# oxvox.net
KiCad netlist of a schematic drawn in EAGLE
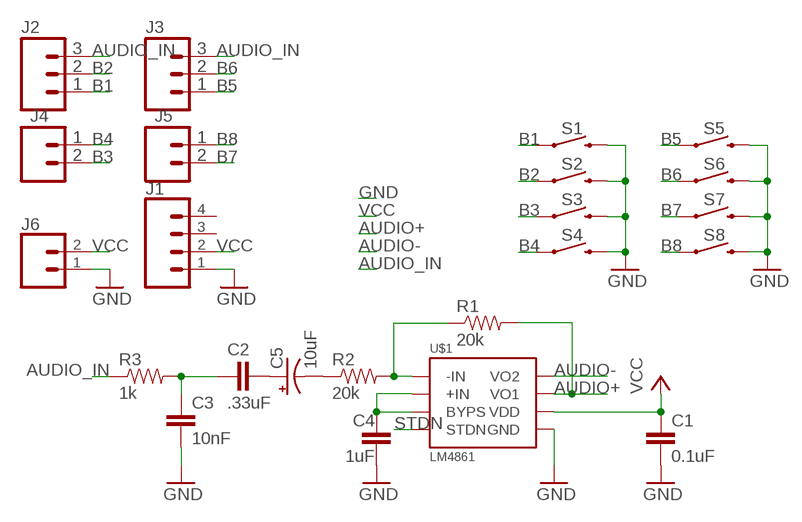
[diagram p0: schematic, sheet 1]

(export (version "E")
  (design (tool "Eeschema 10.0.6"))
  (components
    (comp (ref "C1")
      (value "0.1uF")
      (footprint "eagle-import:0603-CAP")
      (libsource (lib "eagle-import") (part "CAP0603-CAP"))
    )
    (comp (ref "C2")
      (value ".33uF")
      (footprint "eagle-import:0603-CAP")
      (libsource (lib "eagle-import") (part "CAP0603-CAP"))
    )
    (comp (ref "C3")
      (value "10nF")
      (footprint "eagle-import:0603-CAP")
      (libsource (lib "eagle-import") (part "CAP0603-CAP"))
    )
    (comp (ref "C4")
      (value "1uF")
      (footprint "eagle-import:0603-CAP")
      (libsource (lib "eagle-import") (part "CAP0603-CAP"))
    )
    (comp (ref "C5")
      (value "10uF")
      (footprint "eagle-import:RADIAL_SMT_4MM")
      (libsource (lib "eagle-import") (part "RADIAL-CAP4MM"))
    )
    (comp (ref "J1")
      (value "CONN_04")
      (footprint "eagle-import:1X04")
      (libsource (lib "eagle-import") (part "CONN_04"))
    )
    (comp (ref "J2")
      (value "M03-PTH_LONG_NO_SILK_BOT")
      (footprint "eagle-import:M03_LONG_NO_SILK_BOTTOM")
      (libsource (lib "eagle-import") (part "M03-PTH_LONG_NO_SILK_BOT"))
    )
    (comp (ref "J3")
      (value "M03-PTH_LONG_NO_SILK_BOT")
      (footprint "eagle-import:M03_LONG_NO_SILK_BOTTOM")
      (libsource (lib "eagle-import") (part "M03-PTH_LONG_NO_SILK_BOT"))
    )
    (comp (ref "J4")
      (value "M02-PTH_LONG_NO_SILK_BOT")
      (footprint "eagle-import:M02_LONG_NO_SILK_BOTTOM")
      (libsource (lib "eagle-import") (part "M02-PTH_LONG_NO_SILK_BOT"))
    )
    (comp (ref "J5")
      (value "M02-PTH_LONG_NO_SILK_BOT")
      (footprint "eagle-import:M02_LONG_NO_SILK_BOTTOM")
      (libsource (lib "eagle-import") (part "M02-PTH_LONG_NO_SILK_BOT"))
    )
    (comp (ref "J6")
      (value "CONN_02")
      (footprint "eagle-import:1X02")
      (libsource (lib "eagle-import") (part "CONN_02"))
    )
    (comp (ref "R1")
      (value "20k")
      (footprint "eagle-import:0805")
      (libsource (lib "eagle-import") (part "RESISTOR0805-RES"))
    )
    (comp (ref "R2")
      (value "20k")
      (footprint "eagle-import:0805")
      (libsource (lib "eagle-import") (part "RESISTOR0805-RES"))
    )
    (comp (ref "R3")
      (value "1k")
      (footprint "eagle-import:0603-RES")
      (libsource (lib "eagle-import") (part "RESISTOR0603-RES"))
    )
    (comp (ref "S1")
      (value "MOMENTARY-SWITCH-SPST-PTH-6.0MM-KIT-ALL2")
      (footprint "eagle-import:TACTILE_SWITCH_PTH_6.0MM_KIT_NOSILK")
      (libsource (lib "eagle-import") (part "MOMENTARY-SWITCH-SPST-PTH-6.0MM-KIT-ALL2"))
    )
    (comp (ref "S2")
      (value "MOMENTARY-SWITCH-SPST-PTH-6.0MM-KIT-ALL2")
      (footprint "eagle-import:TACTILE_SWITCH_PTH_6.0MM_KIT_NOSILK")
      (libsource (lib "eagle-import") (part "MOMENTARY-SWITCH-SPST-PTH-6.0MM-KIT-ALL2"))
    )
    (comp (ref "S3")
      (value "MOMENTARY-SWITCH-SPST-PTH-6.0MM-KIT-ALL2")
      (footprint "eagle-import:TACTILE_SWITCH_PTH_6.0MM_KIT_NOSILK")
      (libsource (lib "eagle-import") (part "MOMENTARY-SWITCH-SPST-PTH-6.0MM-KIT-ALL2"))
    )
    (comp (ref "S4")
      (value "MOMENTARY-SWITCH-SPST-PTH-6.0MM-KIT-ALL2")
      (footprint "eagle-import:TACTILE_SWITCH_PTH_6.0MM_KIT_NOSILK")
      (libsource (lib "eagle-import") (part "MOMENTARY-SWITCH-SPST-PTH-6.0MM-KIT-ALL2"))
    )
    (comp (ref "S5")
      (value "MOMENTARY-SWITCH-SPST-PTH-6.0MM-KIT-ALL2")
      (footprint "eagle-import:TACTILE_SWITCH_PTH_6.0MM_KIT_NOSILK")
      (libsource (lib "eagle-import") (part "MOMENTARY-SWITCH-SPST-PTH-6.0MM-KIT-ALL2"))
    )
    (comp (ref "S6")
      (value "MOMENTARY-SWITCH-SPST-PTH-6.0MM-KIT-ALL2")
      (footprint "eagle-import:TACTILE_SWITCH_PTH_6.0MM_KIT_NOSILK")
      (libsource (lib "eagle-import") (part "MOMENTARY-SWITCH-SPST-PTH-6.0MM-KIT-ALL2"))
    )
    (comp (ref "S7")
      (value "MOMENTARY-SWITCH-SPST-PTH-6.0MM-KIT-ALL2")
      (footprint "eagle-import:TACTILE_SWITCH_PTH_6.0MM_KIT_NOSILK")
      (libsource (lib "eagle-import") (part "MOMENTARY-SWITCH-SPST-PTH-6.0MM-KIT-ALL2"))
    )
    (comp (ref "S8")
      (value "MOMENTARY-SWITCH-SPST-PTH-6.0MM-KIT-ALL2")
      (footprint "eagle-import:TACTILE_SWITCH_PTH_6.0MM_KIT_NOSILK")
      (libsource (lib "eagle-import") (part "MOMENTARY-SWITCH-SPST-PTH-6.0MM-KIT-ALL2"))
    )
    (comp (ref "U$1")
      (value "LM4861")
      (footprint "eagle-import:8-SOIC")
      (libsource (lib "eagle-import") (part "LM4861"))
    )
  )
  (nets
    (net (code "1") (name "/AUDIO+") (class "Default")
      (node (ref "R1") (pin "2") (pinfunction "2_2") (pintype "passive"))
      (node (ref "U$1") (pin "P$5") (pinfunction "VO1_P$5") (pintype "bidirectional"))
    )
    (net (code "2") (name "/AUDIO-") (class "Default")
      (node (ref "U$1") (pin "P$8") (pinfunction "VO2_P$8") (pintype "bidirectional"))
    )
    (net (code "3") (name "/AUDIO_IN") (class "Default")
      (node (ref "J2") (pin "P$3") (pinfunction "P$3_P$3") (pintype "bidirectional"))
      (node (ref "J3") (pin "P$3") (pinfunction "P$3_P$3") (pintype "bidirectional"))
      (node (ref "R3") (pin "1") (pinfunction "1_1") (pintype "passive"))
    )
    (net (code "4") (name "/B1") (class "Default")
      (node (ref "J2") (pin "P$1") (pinfunction "P$1_P$1") (pintype "bidirectional"))
      (node (ref "S1") (pin "1") (pinfunction "1_1") (pintype "passive"))
      (node (ref "S1") (pin "2") (pinfunction "1_2") (pintype "passive"))
    )
    (net (code "5") (name "/B2") (class "Default")
      (node (ref "J2") (pin "P$2") (pinfunction "P$2_P$2") (pintype "bidirectional"))
      (node (ref "S2") (pin "1") (pinfunction "1_1") (pintype "passive"))
      (node (ref "S2") (pin "2") (pinfunction "1_2") (pintype "passive"))
    )
    (net (code "6") (name "/B3") (class "Default")
      (node (ref "J4") (pin "P$2") (pinfunction "P$2_P$2") (pintype "bidirectional"))
      (node (ref "S3") (pin "1") (pinfunction "1_1") (pintype "passive"))
      (node (ref "S3") (pin "2") (pinfunction "1_2") (pintype "passive"))
    )
    (net (code "7") (name "/B4") (class "Default")
      (node (ref "J4") (pin "P$1") (pinfunction "P$1_P$1") (pintype "bidirectional"))
      (node (ref "S4") (pin "1") (pinfunction "1_1") (pintype "passive"))
      (node (ref "S4") (pin "2") (pinfunction "1_2") (pintype "passive"))
    )
    (net (code "8") (name "/B5") (class "Default")
      (node (ref "J3") (pin "P$1") (pinfunction "P$1_P$1") (pintype "bidirectional"))
      (node (ref "S5") (pin "1") (pinfunction "1_1") (pintype "passive"))
      (node (ref "S5") (pin "2") (pinfunction "1_2") (pintype "passive"))
    )
    (net (code "9") (name "/B6") (class "Default")
      (node (ref "J3") (pin "P$2") (pinfunction "P$2_P$2") (pintype "bidirectional"))
      (node (ref "S6") (pin "1") (pinfunction "1_1") (pintype "passive"))
      (node (ref "S6") (pin "2") (pinfunction "1_2") (pintype "passive"))
    )
    (net (code "10") (name "/B7") (class "Default")
      (node (ref "J5") (pin "P$2") (pinfunction "P$2_P$2") (pintype "bidirectional"))
      (node (ref "S7") (pin "1") (pinfunction "1_1") (pintype "passive"))
      (node (ref "S7") (pin "2") (pinfunction "1_2") (pintype "passive"))
    )
    (net (code "11") (name "/B8") (class "Default")
      (node (ref "J5") (pin "P$1") (pinfunction "P$1_P$1") (pintype "bidirectional"))
      (node (ref "S8") (pin "1") (pinfunction "1_1") (pintype "passive"))
      (node (ref "S8") (pin "2") (pinfunction "1_2") (pintype "passive"))
    )
    (net (code "12") (name "/STDN") (class "Default")
      (node (ref "U$1") (pin "P$1") (pinfunction "STDN_P$1") (pintype "bidirectional"))
    )
    (net (code "13") (name "GND") (class "Default")
      (node (ref "C1") (pin "2") (pinfunction "2_2") (pintype "passive"))
      (node (ref "C3") (pin "2") (pinfunction "2_2") (pintype "passive"))
      (node (ref "C4") (pin "2") (pinfunction "2_2") (pintype "passive"))
      (node (ref "J1") (pin "1") (pinfunction "1_1") (pintype "passive"))
      (node (ref "J6") (pin "1") (pinfunction "1_1") (pintype "passive"))
      (node (ref "S1") (pin "3") (pinfunction "2_3") (pintype "passive"))
      (node (ref "S1") (pin "4") (pinfunction "2_4") (pintype "passive"))
      (node (ref "S2") (pin "3") (pinfunction "2_3") (pintype "passive"))
      (node (ref "S2") (pin "4") (pinfunction "2_4") (pintype "passive"))
      (node (ref "S3") (pin "3") (pinfunction "2_3") (pintype "passive"))
      (node (ref "S3") (pin "4") (pinfunction "2_4") (pintype "passive"))
      (node (ref "S4") (pin "3") (pinfunction "2_3") (pintype "passive"))
      (node (ref "S4") (pin "4") (pinfunction "2_4") (pintype "passive"))
      (node (ref "S5") (pin "3") (pinfunction "2_3") (pintype "passive"))
      (node (ref "S5") (pin "4") (pinfunction "2_4") (pintype "passive"))
      (node (ref "S6") (pin "3") (pinfunction "2_3") (pintype "passive"))
      (node (ref "S6") (pin "4") (pinfunction "2_4") (pintype "passive"))
      (node (ref "S7") (pin "3") (pinfunction "2_3") (pintype "passive"))
      (node (ref "S7") (pin "4") (pinfunction "2_4") (pintype "passive"))
      (node (ref "S8") (pin "3") (pinfunction "2_3") (pintype "passive"))
      (node (ref "S8") (pin "4") (pinfunction "2_4") (pintype "passive"))
      (node (ref "U$1") (pin "P$7") (pinfunction "GND_P$7") (pintype "bidirectional"))
    )
    (net (code "14") (name "Net-(C2-Pad2)") (class "Default")
      (node (ref "C2") (pin "2") (pinfunction "2_2") (pintype "passive"))
      (node (ref "C3") (pin "1") (pinfunction "1_1") (pintype "passive"))
      (node (ref "R3") (pin "2") (pinfunction "2_2") (pintype "passive"))
    )
    (net (code "15") (name "Net-(C5-+)") (class "Default")
      (node (ref "C2") (pin "1") (pinfunction "1_1") (pintype "passive"))
      (node (ref "C5") (pin "P$1") (pinfunction "+_P$1") (pintype "passive"))
    )
    (net (code "16") (name "Net-(C5--)") (class "Default")
      (node (ref "C5") (pin "P$2") (pinfunction "-_P$2") (pintype "passive"))
      (node (ref "R2") (pin "1") (pinfunction "1_1") (pintype "passive"))
    )
    (net (code "17") (name "Net-(U$1-+IN)") (class "Default")
      (node (ref "C4") (pin "1") (pinfunction "1_1") (pintype "passive"))
      (node (ref "U$1") (pin "P$2") (pinfunction "BYPS_P$2") (pintype "bidirectional"))
      (node (ref "U$1") (pin "P$3") (pinfunction "+IN_P$3") (pintype "bidirectional"))
    )
    (net (code "18") (name "Net-(U$1--IN)") (class "Default")
      (node (ref "R1") (pin "1") (pinfunction "1_1") (pintype "passive"))
      (node (ref "R2") (pin "2") (pinfunction "2_2") (pintype "passive"))
      (node (ref "U$1") (pin "P$4") (pinfunction "-IN_P$4") (pintype "bidirectional"))
    )
    (net (code "19") (name "VCC") (class "Default")
      (node (ref "C1") (pin "1") (pinfunction "1_1") (pintype "passive"))
      (node (ref "J1") (pin "2") (pinfunction "2_2") (pintype "passive"))
      (node (ref "J6") (pin "2") (pinfunction "2_2") (pintype "passive"))
      (node (ref "U$1") (pin "P$6") (pinfunction "VDD_P$6") (pintype "bidirectional"))
    )
    (net (code "20") (name "unconnected-(J1-Pad3)") (class "Default")
      (node (ref "J1") (pin "3") (pinfunction "3_3") (pintype "passive"))
    )
    (net (code "21") (name "unconnected-(J1-Pad4)") (class "Default")
      (node (ref "J1") (pin "4") (pinfunction "4_4") (pintype "passive"))
    )
  )
)
